# RGB_01.net
KiCad netlist of a schematic drawn in Altium Designer
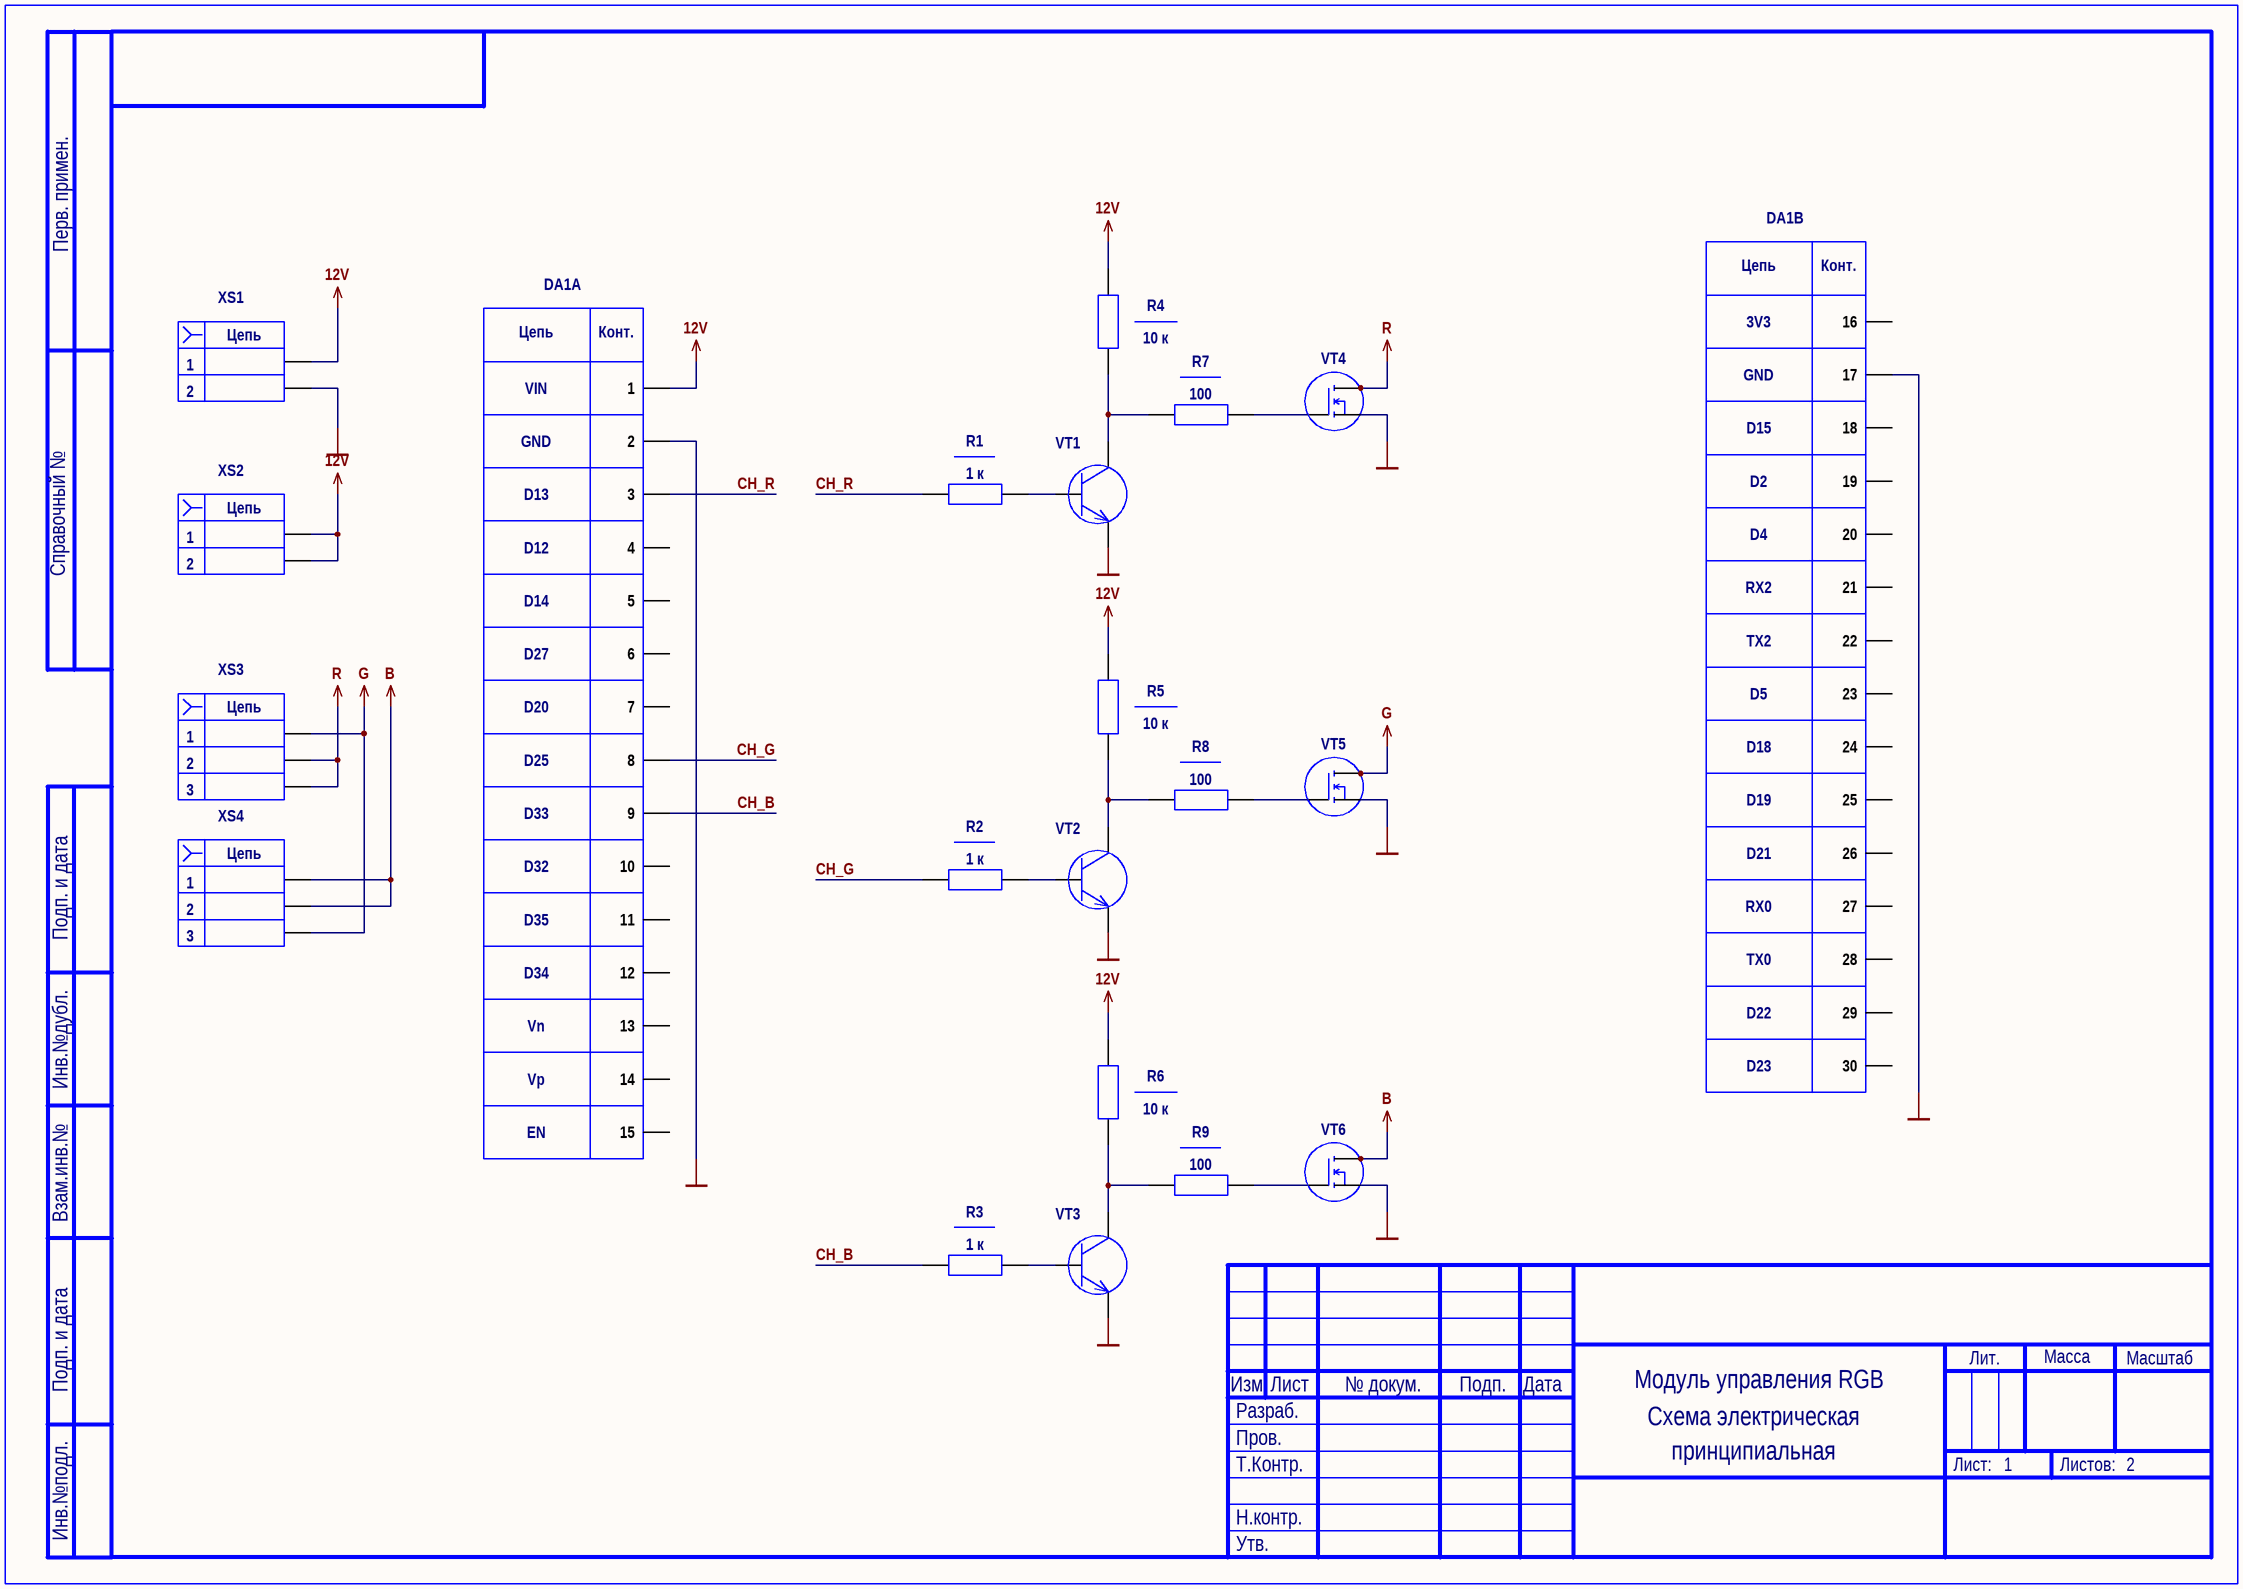
[diagram p0: RGB_01.SchDoc]

(export (version "E")
  (design (tool "Eeschema 10.0.6"))
  (components
    (comp (ref "DA1")
      (value "ESP32-WROOM-DEVKIT-30pinArduino")
      (footprint "ESP32-WROOM-DEVKIT-30pin")
      (libsource (lib "Smirnov") (part "ESP32-WROOM-DEVKIT-30pin"))
    )
    (comp (ref "R1")
      (value "0805 1 кОм 5%")
      (footprint "Chip_Resistor_0805")
      (description "Резистор 0805")
      (fields
        (field (name "СОПРОТИВЛЕНИЕ (ДЛЯ СХЕМЫ)") "1 к")
        (field (name "PART NUMBER") "ERJ-6GEYJ102V")
        (field (name "ДЛЯ СПИСКА PART NUMBER") "Резистор ERJ-6GEYJ102V")
        (field (name "AUTOR") "Смирнов К.О.")
      )
      (libsource (lib "GLOBAL_AD_LIBS") (part "Резистор"))
    )
    (comp (ref "R2")
      (value "0805 1 кОм 5%")
      (footprint "Chip_Resistor_0805")
      (description "Резистор 0805")
      (fields
        (field (name "СОПРОТИВЛЕНИЕ (ДЛЯ СХЕМЫ)") "1 к")
        (field (name "PART NUMBER") "ERJ-6GEYJ102V")
        (field (name "ДЛЯ СПИСКА PART NUMBER") "Резистор ERJ-6GEYJ102V")
        (field (name "AUTOR") "Смирнов К.О.")
      )
      (libsource (lib "GLOBAL_AD_LIBS") (part "Резистор"))
    )
    (comp (ref "R3")
      (value "0805 1 кОм 5%")
      (footprint "Chip_Resistor_0805")
      (description "Резистор 0805")
      (fields
        (field (name "СОПРОТИВЛЕНИЕ (ДЛЯ СХЕМЫ)") "1 к")
        (field (name "PART NUMBER") "ERJ-6GEYJ102V")
        (field (name "ДЛЯ СПИСКА PART NUMBER") "Резистор ERJ-6GEYJ102V")
        (field (name "AUTOR") "Смирнов К.О.")
      )
      (libsource (lib "GLOBAL_AD_LIBS") (part "Резистор"))
    )
    (comp (ref "R4")
      (value "0805 10 кОм 5%")
      (footprint "Chip_Resistor_0805")
      (description "Резистор 0805")
      (fields
        (field (name "СОПРОТИВЛЕНИЕ (ДЛЯ СХЕМЫ)") "10 к")
        (field (name "PART NUMBER") "ERJ-6GEYJ103V")
        (field (name "ДЛЯ СПИСКА PART NUMBER") "Резистор ERJ-6GEYJ103V")
        (field (name "AUTOR") "Смирнов К.О.")
      )
      (libsource (lib "GLOBAL_AD_LIBS") (part "Резистор вертикальный"))
    )
    (comp (ref "R5")
      (value "0805 10 кОм 5%")
      (footprint "Chip_Resistor_0805")
      (description "Резистор 0805")
      (fields
        (field (name "СОПРОТИВЛЕНИЕ (ДЛЯ СХЕМЫ)") "10 к")
        (field (name "PART NUMBER") "ERJ-6GEYJ103V")
        (field (name "ДЛЯ СПИСКА PART NUMBER") "Резистор ERJ-6GEYJ103V")
        (field (name "AUTOR") "Смирнов К.О.")
      )
      (libsource (lib "GLOBAL_AD_LIBS") (part "Резистор вертикальный"))
    )
    (comp (ref "R6")
      (value "0805 10 кОм 5%")
      (footprint "Chip_Resistor_0805")
      (description "Резистор 0805")
      (fields
        (field (name "СОПРОТИВЛЕНИЕ (ДЛЯ СХЕМЫ)") "10 к")
        (field (name "PART NUMBER") "ERJ-6GEYJ103V")
        (field (name "ДЛЯ СПИСКА PART NUMBER") "Резистор ERJ-6GEYJ103V")
        (field (name "AUTOR") "Смирнов К.О.")
      )
      (libsource (lib "GLOBAL_AD_LIBS") (part "Резистор вертикальный"))
    )
    (comp (ref "R7")
      (value "0805 100 Ом 5%")
      (footprint "Chip_Resistor_0805")
      (description "Резистор 0805")
      (fields
        (field (name "СОПРОТИВЛЕНИЕ (ДЛЯ СХЕМЫ)") "100")
        (field (name "PART NUMBER") "ERJ-6GEYJ101V")
        (field (name "ДЛЯ СПИСКА PART NUMBER") "Резистор ERJ-6GEYJ101V")
        (field (name "AUTOR") "Смирнов К.О.")
      )
      (libsource (lib "GLOBAL_AD_LIBS") (part "Резистор"))
    )
    (comp (ref "R8")
      (value "0805 100 Ом 5%")
      (footprint "Chip_Resistor_0805")
      (description "Резистор 0805")
      (fields
        (field (name "СОПРОТИВЛЕНИЕ (ДЛЯ СХЕМЫ)") "100")
        (field (name "PART NUMBER") "ERJ-6GEYJ101V")
        (field (name "ДЛЯ СПИСКА PART NUMBER") "Резистор ERJ-6GEYJ101V")
        (field (name "AUTOR") "Смирнов К.О.")
      )
      (libsource (lib "GLOBAL_AD_LIBS") (part "Резистор"))
    )
    (comp (ref "R9")
      (value "0805 100 Ом 5%")
      (footprint "Chip_Resistor_0805")
      (description "Резистор 0805")
      (fields
        (field (name "СОПРОТИВЛЕНИЕ (ДЛЯ СХЕМЫ)") "100")
        (field (name "PART NUMBER") "ERJ-6GEYJ101V")
        (field (name "ДЛЯ СПИСКА PART NUMBER") "Резистор ERJ-6GEYJ101V")
        (field (name "AUTOR") "Смирнов К.О.")
      )
      (libsource (lib "GLOBAL_AD_LIBS") (part "Резистор"))
    )
    (comp (ref "VT1")
      (value "2Т3130А9/ПК")
      (footprint "2Т3130_(КТ-46)")
      (description "Кремниевый эпитаксиально-планарный n-p-n транзистор")
      (fields
        (field (name "MANUFACTURER") "ООО \"АРСЕНАЛ \"КРЗПП\"")
        (field (name "ДЛЯ СПИСКА PART NUMBER") "Транзистор 2Т3130А9/ПК АЕЯР.432140.259ТУ")
        (field (name "AUTOR") "Смирнов")
      )
      (libsource (lib "GLOBAL_AD_LIBS") (part "NPN_B1E2C3"))
    )
    (comp (ref "VT2")
      (value "2Т3130А9/ПК")
      (footprint "2Т3130_(КТ-46)")
      (description "Кремниевый эпитаксиально-планарный n-p-n транзистор")
      (fields
        (field (name "MANUFACTURER") "ООО \"АРСЕНАЛ \"КРЗПП\"")
        (field (name "ДЛЯ СПИСКА PART NUMBER") "Транзистор 2Т3130А9/ПК АЕЯР.432140.259ТУ")
        (field (name "AUTOR") "Смирнов")
      )
      (libsource (lib "GLOBAL_AD_LIBS") (part "NPN_B1E2C3"))
    )
    (comp (ref "VT3")
      (value "2Т3130А9/ПК")
      (footprint "2Т3130_(КТ-46)")
      (description "Кремниевый эпитаксиально-планарный n-p-n транзистор")
      (fields
        (field (name "MANUFACTURER") "ООО \"АРСЕНАЛ \"КРЗПП\"")
        (field (name "ДЛЯ СПИСКА PART NUMBER") "Транзистор 2Т3130А9/ПК АЕЯР.432140.259ТУ")
        (field (name "AUTOR") "Смирнов")
      )
      (libsource (lib "GLOBAL_AD_LIBS") (part "NPN_B1E2C3"))
    )
    (comp (ref "VT4")
      (value "IRF8707")
      (footprint "IRF8707_SO8")
      (libsource (lib "Smirnov") (part "IRF8707"))
    )
    (comp (ref "VT5")
      (value "IRF8707")
      (footprint "IRF8707_SO8")
      (libsource (lib "Smirnov") (part "IRF8707"))
    )
    (comp (ref "VT6")
      (value "IRF8707")
      (footprint "IRF8707_SO8")
      (libsource (lib "Smirnov") (part "IRF8707"))
    )
    (comp (ref "XS1")
      (value "KLS2-128-7.50-02P-4S")
      (footprint "KLS2-128-7.50-02P-4S")
      (libsource (lib "Smirnov") (part "KLS2-128-7.50-02P-4S"))
    )
    (comp (ref "XS2")
      (value "KLS2-128-7.50-02P-4S")
      (footprint "KLS2-128-7.50-02P-4S")
      (libsource (lib "Smirnov") (part "KLS2-128-7.50-02P-4S"))
    )
    (comp (ref "XS3")
      (value "KLS2-128I-5.00-03P-4S")
      (footprint "KLS2-128I-5.00-03P-4S")
      (libsource (lib "Smirnov") (part "KLS2-128I-5.00-03P-4S"))
    )
    (comp (ref "XS4")
      (value "KLS2-128I-5.00-03P-4S")
      (footprint "KLS2-128I-5.00-03P-4S")
      (libsource (lib "Smirnov") (part "KLS2-128I-5.00-03P-4S"))
    )
  )
  (nets
    (net (code "1") (name "/CH_B") (class "Default")
      (node (ref "DA1") (pin "9") (pinfunction "9_9") (pintype "passive"))
      (node (ref "R3") (pin "1") (pinfunction "1_1") (pintype "passive"))
    )
    (net (code "2") (name "/CH_G") (class "Default")
      (node (ref "DA1") (pin "8") (pinfunction "8_8") (pintype "passive"))
      (node (ref "R2") (pin "1") (pinfunction "1_1") (pintype "passive"))
    )
    (net (code "3") (name "/CH_R") (class "Default")
      (node (ref "DA1") (pin "3") (pinfunction "3_3") (pintype "passive"))
      (node (ref "R1") (pin "1") (pinfunction "1_1") (pintype "passive"))
    )
    (net (code "4") (name "12V") (class "Default")
      (node (ref "DA1") (pin "1") (pinfunction "1_1") (pintype "passive"))
      (node (ref "R4") (pin "1") (pinfunction "1_1") (pintype "passive"))
      (node (ref "R5") (pin "1") (pinfunction "1_1") (pintype "passive"))
      (node (ref "R6") (pin "1") (pinfunction "1_1") (pintype "passive"))
      (node (ref "XS1") (pin "1") (pinfunction "1_1") (pintype "passive"))
      (node (ref "XS2") (pin "1") (pinfunction "1_1") (pintype "passive"))
      (node (ref "XS2") (pin "2") (pinfunction "2_2") (pintype "passive"))
    )
    (net (code "5") (name "B") (class "Default")
      (node (ref "VT6") (pin "5") (pinfunction "С_5") (pintype "passive"))
      (node (ref "VT6") (pin "6") (pinfunction "С_6") (pintype "passive"))
      (node (ref "VT6") (pin "7") (pinfunction "С_7") (pintype "passive"))
      (node (ref "VT6") (pin "8") (pinfunction "С_8") (pintype "passive"))
      (node (ref "XS4") (pin "1") (pinfunction "1_1") (pintype "passive"))
      (node (ref "XS4") (pin "2") (pinfunction "2_2") (pintype "passive"))
    )
    (net (code "6") (name "G") (class "Default")
      (node (ref "VT5") (pin "5") (pinfunction "С_5") (pintype "passive"))
      (node (ref "VT5") (pin "6") (pinfunction "С_6") (pintype "passive"))
      (node (ref "VT5") (pin "7") (pinfunction "С_7") (pintype "passive"))
      (node (ref "VT5") (pin "8") (pinfunction "С_8") (pintype "passive"))
      (node (ref "XS3") (pin "1") (pinfunction "1_1") (pintype "passive"))
      (node (ref "XS4") (pin "3") (pinfunction "3_3") (pintype "passive"))
    )
    (net (code "7") (name "GND") (class "Default")
      (node (ref "DA1") (pin "17") (pinfunction "17_17") (pintype "passive"))
      (node (ref "DA1") (pin "2") (pinfunction "2_2") (pintype "passive"))
      (node (ref "VT1") (pin "2") (pinfunction "E_2") (pintype "passive"))
      (node (ref "VT2") (pin "2") (pinfunction "E_2") (pintype "passive"))
      (node (ref "VT3") (pin "2") (pinfunction "E_2") (pintype "passive"))
      (node (ref "VT4") (pin "1") (pinfunction "И_1") (pintype "passive"))
      (node (ref "VT4") (pin "2") (pinfunction "И_2") (pintype "passive"))
      (node (ref "VT4") (pin "3") (pinfunction "И_3") (pintype "passive"))
      (node (ref "VT5") (pin "1") (pinfunction "И_1") (pintype "passive"))
      (node (ref "VT5") (pin "2") (pinfunction "И_2") (pintype "passive"))
      (node (ref "VT5") (pin "3") (pinfunction "И_3") (pintype "passive"))
      (node (ref "VT6") (pin "1") (pinfunction "И_1") (pintype "passive"))
      (node (ref "VT6") (pin "2") (pinfunction "И_2") (pintype "passive"))
      (node (ref "VT6") (pin "3") (pinfunction "И_3") (pintype "passive"))
      (node (ref "XS1") (pin "2") (pinfunction "2_2") (pintype "passive"))
    )
    (net (code "8") (name "Net-(VT1-B)") (class "Default")
      (node (ref "R1") (pin "2") (pinfunction "2_2") (pintype "passive"))
      (node (ref "VT1") (pin "1") (pinfunction "B_1") (pintype "passive"))
    )
    (net (code "9") (name "Net-(VT1-C)") (class "Default")
      (node (ref "R4") (pin "2") (pinfunction "2_2") (pintype "passive"))
      (node (ref "R7") (pin "1") (pinfunction "1_1") (pintype "passive"))
      (node (ref "VT1") (pin "3") (pinfunction "C_3") (pintype "passive"))
    )
    (net (code "10") (name "Net-(VT2-B)") (class "Default")
      (node (ref "R2") (pin "2") (pinfunction "2_2") (pintype "passive"))
      (node (ref "VT2") (pin "1") (pinfunction "B_1") (pintype "passive"))
    )
    (net (code "11") (name "Net-(VT2-C)") (class "Default")
      (node (ref "R5") (pin "2") (pinfunction "2_2") (pintype "passive"))
      (node (ref "R8") (pin "1") (pinfunction "1_1") (pintype "passive"))
      (node (ref "VT2") (pin "3") (pinfunction "C_3") (pintype "passive"))
    )
    (net (code "12") (name "Net-(VT3-B)") (class "Default")
      (node (ref "R3") (pin "2") (pinfunction "2_2") (pintype "passive"))
      (node (ref "VT3") (pin "1") (pinfunction "B_1") (pintype "passive"))
    )
    (net (code "13") (name "Net-(VT3-C)") (class "Default")
      (node (ref "R6") (pin "2") (pinfunction "2_2") (pintype "passive"))
      (node (ref "R9") (pin "1") (pinfunction "1_1") (pintype "passive"))
      (node (ref "VT3") (pin "3") (pinfunction "C_3") (pintype "passive"))
    )
    (net (code "14") (name "Net-(VT4-З)") (class "Default")
      (node (ref "R7") (pin "2") (pinfunction "2_2") (pintype "passive"))
      (node (ref "VT4") (pin "4") (pinfunction "З_4") (pintype "passive"))
    )
    (net (code "15") (name "Net-(VT5-З)") (class "Default")
      (node (ref "R8") (pin "2") (pinfunction "2_2") (pintype "passive"))
      (node (ref "VT5") (pin "4") (pinfunction "З_4") (pintype "passive"))
    )
    (net (code "16") (name "Net-(VT6-З)") (class "Default")
      (node (ref "R9") (pin "2") (pinfunction "2_2") (pintype "passive"))
      (node (ref "VT6") (pin "4") (pinfunction "З_4") (pintype "passive"))
    )
    (net (code "17") (name "R") (class "Default")
      (node (ref "VT4") (pin "5") (pinfunction "С_5") (pintype "passive"))
      (node (ref "VT4") (pin "6") (pinfunction "С_6") (pintype "passive"))
      (node (ref "VT4") (pin "7") (pinfunction "С_7") (pintype "passive"))
      (node (ref "VT4") (pin "8") (pinfunction "С_8") (pintype "passive"))
      (node (ref "XS3") (pin "2") (pinfunction "2_2") (pintype "passive"))
      (node (ref "XS3") (pin "3") (pinfunction "3_3") (pintype "passive"))
    )
    (net (code "18") (name "unconnected-(DA1-Pad4)") (class "Default")
      (node (ref "DA1") (pin "4") (pinfunction "4_4") (pintype "passive"))
    )
    (net (code "19") (name "unconnected-(DA1-Pad5)") (class "Default")
      (node (ref "DA1") (pin "5") (pinfunction "5_5") (pintype "passive"))
    )
    (net (code "20") (name "unconnected-(DA1-Pad6)") (class "Default")
      (node (ref "DA1") (pin "6") (pinfunction "6_6") (pintype "passive"))
    )
    (net (code "21") (name "unconnected-(DA1-Pad7)") (class "Default")
      (node (ref "DA1") (pin "7") (pinfunction "7_7") (pintype "passive"))
    )
    (net (code "22") (name "unconnected-(DA1-Pad10)") (class "Default")
      (node (ref "DA1") (pin "10") (pinfunction "10_10") (pintype "passive"))
    )
    (net (code "23") (name "unconnected-(DA1-Pad11)") (class "Default")
      (node (ref "DA1") (pin "11") (pinfunction "11_11") (pintype "passive"))
    )
    (net (code "24") (name "unconnected-(DA1-Pad12)") (class "Default")
      (node (ref "DA1") (pin "12") (pinfunction "12_12") (pintype "passive"))
    )
    (net (code "25") (name "unconnected-(DA1-Pad13)") (class "Default")
      (node (ref "DA1") (pin "13") (pinfunction "13_13") (pintype "passive"))
    )
    (net (code "26") (name "unconnected-(DA1-Pad14)") (class "Default")
      (node (ref "DA1") (pin "14") (pinfunction "14_14") (pintype "passive"))
    )
    (net (code "27") (name "unconnected-(DA1-Pad15)") (class "Default")
      (node (ref "DA1") (pin "15") (pinfunction "15_15") (pintype "passive"))
    )
    (net (code "28") (name "unconnected-(DA1-Pad16)") (class "Default")
      (node (ref "DA1") (pin "16") (pinfunction "16_16") (pintype "passive"))
    )
    (net (code "29") (name "unconnected-(DA1-Pad18)") (class "Default")
      (node (ref "DA1") (pin "18") (pinfunction "18_18") (pintype "passive"))
    )
    (net (code "30") (name "unconnected-(DA1-Pad19)") (class "Default")
      (node (ref "DA1") (pin "19") (pinfunction "19_19") (pintype "passive"))
    )
    (net (code "31") (name "unconnected-(DA1-Pad20)") (class "Default")
      (node (ref "DA1") (pin "20") (pinfunction "20_20") (pintype "passive"))
    )
    (net (code "32") (name "unconnected-(DA1-Pad21)") (class "Default")
      (node (ref "DA1") (pin "21") (pinfunction "21_21") (pintype "passive"))
    )
    (net (code "33") (name "unconnected-(DA1-Pad22)") (class "Default")
      (node (ref "DA1") (pin "22") (pinfunction "22_22") (pintype "passive"))
    )
    (net (code "34") (name "unconnected-(DA1-Pad23)") (class "Default")
      (node (ref "DA1") (pin "23") (pinfunction "23_23") (pintype "passive"))
    )
    (net (code "35") (name "unconnected-(DA1-Pad24)") (class "Default")
      (node (ref "DA1") (pin "24") (pinfunction "24_24") (pintype "passive"))
    )
    (net (code "36") (name "unconnected-(DA1-Pad25)") (class "Default")
      (node (ref "DA1") (pin "25") (pinfunction "25_25") (pintype "passive"))
    )
    (net (code "37") (name "unconnected-(DA1-Pad26)") (class "Default")
      (node (ref "DA1") (pin "26") (pinfunction "26_26") (pintype "passive"))
    )
    (net (code "38") (name "unconnected-(DA1-Pad27)") (class "Default")
      (node (ref "DA1") (pin "27") (pinfunction "27_27") (pintype "passive"))
    )
    (net (code "39") (name "unconnected-(DA1-Pad28)") (class "Default")
      (node (ref "DA1") (pin "28") (pinfunction "28_28") (pintype "passive"))
    )
    (net (code "40") (name "unconnected-(DA1-Pad29)") (class "Default")
      (node (ref "DA1") (pin "29") (pinfunction "29_29") (pintype "passive"))
    )
    (net (code "41") (name "unconnected-(DA1-Pad30)") (class "Default")
      (node (ref "DA1") (pin "30") (pinfunction "30_30") (pintype "passive"))
    )
  )
)
